# Hot-Swap_Solutions.net
KiCad netlist of a schematic drawn in Altium Designer
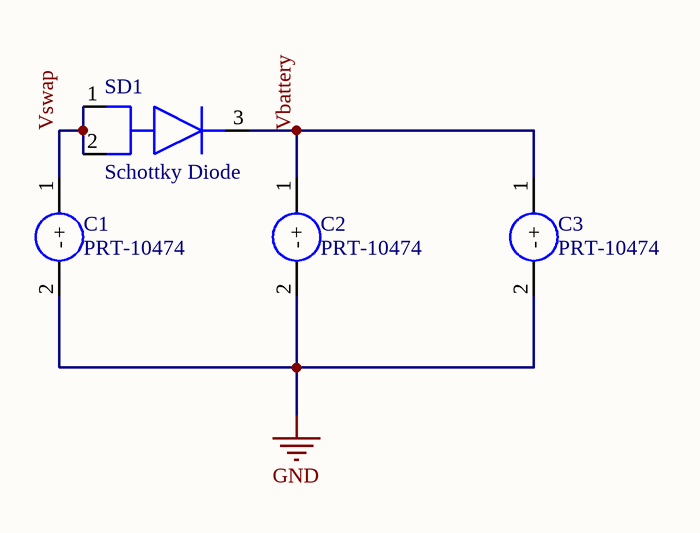
[diagram p0: Hot-Swap_Solutions.SchDoc]

(export (version "E")
  (design (tool "Eeschema 10.0.6"))
  (components
    (comp (ref "C1")
      (value "PRT-10474")
      (footprint "XT60 CONNECTOR REPLACEMENT")
      (description "XT60 CONNECTORS MALE/FEMALE PAIR")
      (fields (field (name "MANUFACTURER") "SparkFun"))
      (libsource (lib "Hot-Swap_Solutions_Schlib") (part "PRT-10474"))
    )
    (comp (ref "C2")
      (value "PRT-10474")
      (footprint "XT60 CONNECTOR REPLACEMENT")
      (description "XT60 CONNECTORS MALE/FEMALE PAIR")
      (fields (field (name "MANUFACTURER") "SparkFun"))
      (libsource (lib "Hot-Swap_Solutions_Schlib") (part "PRT-10474"))
    )
    (comp (ref "C3")
      (value "PRT-10474")
      (footprint "XT60 CONNECTOR REPLACEMENT")
      (description "XT60 CONNECTORS MALE/FEMALE PAIR")
      (fields (field (name "MANUFACTURER") "SparkFun"))
      (libsource (lib "Hot-Swap_Solutions_Schlib") (part "PRT-10474"))
    )
    (comp (ref "SD1")
      (value "Schottky Diode")
      (footprint "Schottky Barrier Diode")
      (fields (field (name "MANUFACTURER") "Rohm") (field (name "MANUFACTURER PART NUMBER") "RB228NS-40FHTL"))
      (libsource (lib "Hot-Swap_Solutions_Schlib") (part "RB228NS-40FHTL"))
    )
  )
  (nets
    (net (code "1") (name "/Vbattery") (class "Default")
      (node (ref "C2") (pin "1") (pinfunction "+_1") (pintype "passive"))
      (node (ref "C3") (pin "1") (pinfunction "+_1") (pintype "passive"))
      (node (ref "SD1") (pin "3") (pintype "passive"))
    )
    (net (code "2") (name "/Vswap") (class "Default")
      (node (ref "C1") (pin "1") (pinfunction "+_1") (pintype "passive"))
      (node (ref "SD1") (pin "1") (pintype "passive"))
      (node (ref "SD1") (pin "2") (pinfunction "2_2") (pintype "passive"))
    )
    (net (code "3") (name "GND") (class "Default")
      (node (ref "C1") (pin "2") (pinfunction "-_2") (pintype "passive"))
      (node (ref "C2") (pin "2") (pinfunction "-_2") (pintype "passive"))
      (node (ref "C3") (pin "2") (pinfunction "-_2") (pintype "passive"))
    )
  )
)
